# power_board.net
KiCad netlist of a schematic drawn in Altium Designer
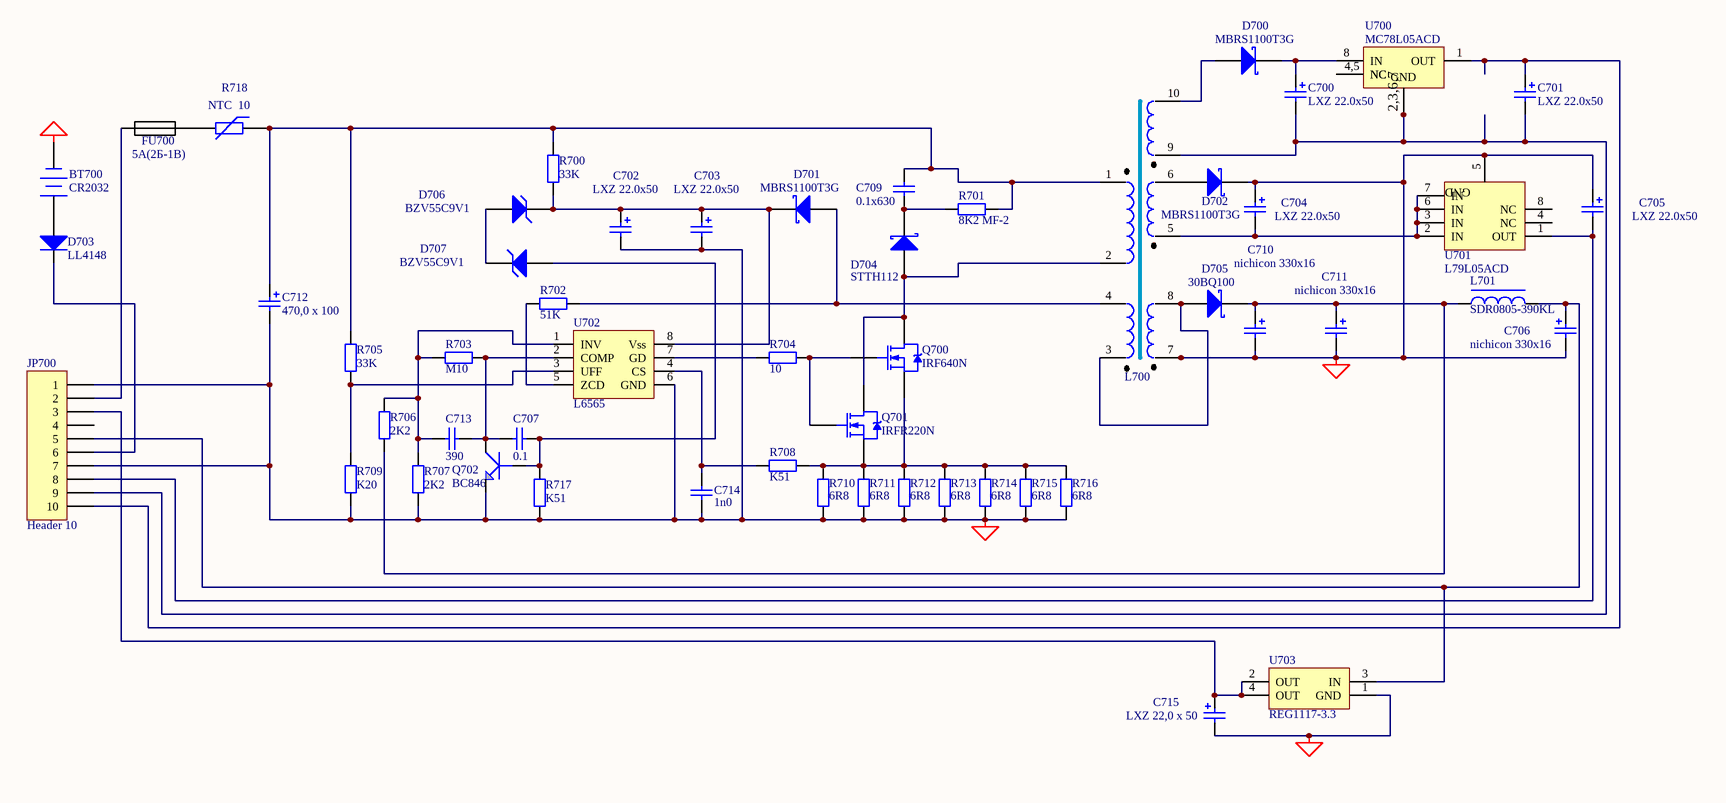
[diagram p0: power_board.SchDoc]

(export (version "E")
  (design (tool "Eeschema 10.0.6"))
  (components
    (comp (ref "BT700")
      (value "CR2032")
      (footprint "BAT_SUPP")
      (description "Multicell Battery")
      (fields (field (name "MANUFACTURER") "Generic Components") (field (name "PUBLISHER") "Altium Limited"))
      (libsource (lib "Miscellaneous Devices") (part "Battery"))
    )
    (comp (ref "C700")
      (value "LXZ 22.0x50")
      (footprint "el3")
      (description "Polarized Capacitor (Radial)")
      (fields (field (name "MANUFACTURER") "Generic Components") (field (name "PUBLISHER") "Altium Limited"))
      (libsource (lib "PAL") (part "Cap Pol1"))
    )
    (comp (ref "C701")
      (value "LXZ 22.0x50")
      (footprint "el3")
      (description "Polarized Capacitor (Radial)")
      (fields (field (name "MANUFACTURER") "Generic Components") (field (name "PUBLISHER") "Altium Limited"))
      (libsource (lib "PAL") (part "Cap Pol1"))
    )
    (comp (ref "C702")
      (value "LXZ 22.0x50")
      (footprint "el3")
      (description "Polarized Capacitor (Radial)")
      (fields (field (name "MANUFACTURER") "Generic Components") (field (name "PUBLISHER") "Altium Limited"))
      (libsource (lib "PAL") (part "Cap Pol1"))
    )
    (comp (ref "C703")
      (value "LXZ 22.0x50")
      (footprint "el3")
      (description "Polarized Capacitor (Radial)")
      (fields (field (name "MANUFACTURER") "Generic Components") (field (name "PUBLISHER") "Altium Limited"))
      (libsource (lib "PAL") (part "Cap Pol1"))
    )
    (comp (ref "C704")
      (value "LXZ 22.0x50")
      (footprint "el3")
      (description "Polarized Capacitor (Radial)")
      (fields (field (name "MANUFACTURER") "Generic Components") (field (name "PUBLISHER") "Altium Limited"))
      (libsource (lib "PAL") (part "Cap Pol1"))
    )
    (comp (ref "C705")
      (value "LXZ 22.0x50")
      (footprint "el3")
      (description "Polarized Capacitor (Radial)")
      (fields (field (name "MANUFACTURER") "Generic Components") (field (name "PUBLISHER") "Altium Limited"))
      (libsource (lib "PAL") (part "Cap Pol1"))
    )
    (comp (ref "C706")
      (value "nichicon 330x16")
      (footprint "el5")
      (description "Polarized Capacitor (Radial)")
      (fields (field (name "MANUFACTURER") "Generic Components") (field (name "PUBLISHER") "Altium Limited"))
      (libsource (lib "PAL") (part "Cap Pol1"))
    )
    (comp (ref "C707")
      (value "0.1")
      (footprint "_1206")
      (description "Capacitor (Semiconductor SIM Model)")
      (fields (field (name "MANUFACTURER") "Generic Components") (field (name "PUBLISHER") "Altium Limited"))
      (libsource (lib "Miscellaneous Devices") (part "Cap Semi"))
    )
    (comp (ref "C709")
      (value "0.1x630")
      (footprint "c15")
      (description "Capacitor (Semiconductor SIM Model)")
      (fields (field (name "MANUFACTURER") "Generic Components") (field (name "PUBLISHER") "Altium Limited"))
      (libsource (lib "Miscellaneous Devices") (part "Cap Semi"))
    )
    (comp (ref "C710")
      (value "nichicon 330x16")
      (footprint "el5")
      (description "Polarized Capacitor (Radial)")
      (fields (field (name "MANUFACTURER") "Generic Components") (field (name "PUBLISHER") "Altium Limited"))
      (libsource (lib "PAL") (part "Cap Pol1"))
    )
    (comp (ref "C711")
      (value "nichicon 330x16")
      (footprint "el5")
      (description "Polarized Capacitor (Radial)")
      (fields (field (name "MANUFACTURER") "Generic Components") (field (name "PUBLISHER") "Altium Limited"))
      (libsource (lib "PAL") (part "Cap Pol1"))
    )
    (comp (ref "C712")
      (value "470,0 x 100")
      (footprint "el_15_25_h")
      (description "Polarized Capacitor (Radial)")
      (fields (field (name "MANUFACTURER") "Generic Components") (field (name "PUBLISHER") "Altium Limited"))
      (libsource (lib "PAL") (part "Cap Pol1"))
    )
    (comp (ref "C713")
      (value "390")
      (footprint "_1206")
      (description "Capacitor (Semiconductor SIM Model)")
      (fields (field (name "MANUFACTURER") "Generic Components") (field (name "PUBLISHER") "Altium Limited"))
      (libsource (lib "Miscellaneous Devices") (part "Cap Semi"))
    )
    (comp (ref "C714")
      (value "1n0")
      (footprint "_1206")
      (description "Capacitor (Semiconductor SIM Model)")
      (fields (field (name "MANUFACTURER") "Generic Components") (field (name "PUBLISHER") "Altium Limited"))
      (libsource (lib "Miscellaneous Devices") (part "Cap Semi"))
    )
    (comp (ref "C715")
      (value "LXZ 22,0 x 50")
      (footprint "el3")
      (description "Polarized Capacitor (Radial)")
      (fields (field (name "MANUFACTURER") "Generic Components") (field (name "PUBLISHER") "Altium Limited"))
      (libsource (lib "PAL") (part "Cap Pol1"))
    )
    (comp (ref "D700")
      (value "MBRS1100T3G")
      (footprint "D_6_3")
      (description "Schottky Rectifier")
      (fields
        (field (name "MANUFACTURER") "International Rectifier")
        (field (name "PUBLISHER") "Altium Limited")
      )
      (libsource (lib "IR Discrete Diode") (part "10BQ015"))
    )
    (comp (ref "D701")
      (value "MBRS1100T3G")
      (footprint "D_6_3")
      (description "Schottky Rectifier")
      (fields
        (field (name "MANUFACTURER") "International Rectifier")
        (field (name "PUBLISHER") "Altium Limited")
      )
      (libsource (lib "IR Discrete Diode") (part "10BQ015"))
    )
    (comp (ref "D702")
      (value "MBRS1100T3G")
      (footprint "D_6_3")
      (description "Schottky Rectifier")
      (fields
        (field (name "MANUFACTURER") "International Rectifier")
        (field (name "PUBLISHER") "Altium Limited")
      )
      (libsource (lib "IR Discrete Diode") (part "10BQ015"))
    )
    (comp (ref "D703")
      (value "LL4148")
      (footprint "_1206d")
      (description "Default Diode")
      (fields (field (name "MANUFACTURER") "Generic Components") (field (name "PUBLISHER") "Altium Limited"))
      (libsource (lib "PAL") (part "Diode"))
    )
    (comp (ref "D704")
      (value "STTH112")
      (footprint "D_6_3")
      (description "Schottky Diode")
      (fields
        (field (name "MANUFACTURER") "International Rectifier")
        (field (name "PUBLISHER") "Altium Limited")
      )
      (libsource (lib "IR Discrete Diode") (part "10BQ015"))
    )
    (comp (ref "D705")
      (value "30BQ100")
      (footprint "30BQ100")
      (description "Schottky Rectifier")
      (fields
        (field (name "MANUFACTURER") "International Rectifier")
        (field (name "PUBLISHER") "Altium Limited")
      )
      (libsource (lib "IR Discrete Diode") (part "10BQ015"))
    )
    (comp (ref "D706")
      (value "BZV55C9V1")
      (footprint "_1206d")
      (description "Zener Diode")
      (fields (field (name "MANUFACTURER") "Generic Components") (field (name "PUBLISHER") "Altium Limited"))
      (libsource (lib "Miscellaneous Devices") (part "D Zener"))
    )
    (comp (ref "D707")
      (value "BZV55C9V1")
      (footprint "_1206d")
      (description "Zener Diode")
      (fields (field (name "MANUFACTURER") "Generic Components") (field (name "PUBLISHER") "Altium Limited"))
      (libsource (lib "Miscellaneous Devices") (part "D Zener"))
    )
    (comp (ref "FU700") (value "5A(2Б-1В)") (footprint "FUSE2") (libsource (lib "PAL") (part "FUSE")))
    (comp (ref "JP700")
      (value "Header 10")
      (footprint "HDR2X5")
      (description "Header, 10-Pin")
      (fields (field (name "MANUFACTURER") "Generic Components") (field (name "PUBLISHER") "Altium Limited"))
      (libsource (lib "Miscellaneous Connectors") (part "Header 10"))
    )
    (comp (ref "L700")
      (value "L220-K10")
      (footprint "trans_ring1")
      (description "Дроссель")
      (libsource (lib "PAL") (part "L1_dc_2"))
    )
    (comp (ref "L701")
      (value "SDR0805-390KL")
      (footprint "L10x10")
      (description "Magnetic-Core Inductor")
      (fields (field (name "MANUFACTURER") "Generic Components") (field (name "PUBLISHER") "Altium Limited"))
      (libsource (lib "PAL") (part "Inductor Konstr 2"))
    )
    (comp (ref "Q700")
      (value "IRF640N")
      (footprint "TO220_h")
      (description "N-Channel Power MOSFET")
      (fields (field (name "MANUFACTURER") "Generic Components") (field (name "PUBLISHER") "Altium Limited"))
      (libsource (lib "Miscellaneous Devices") (part "NMOS-2"))
    )
    (comp (ref "Q701")
      (value "IRFR220N")
      (footprint "SIP-G3/E13")
      (description "N-Channel Power MOSFET")
      (fields (field (name "MANUFACTURER") "Generic Components") (field (name "PUBLISHER") "Altium Limited"))
      (libsource (lib "Miscellaneous Devices") (part "NMOS-2"))
    )
    (comp (ref "Q702")
      (value "BC846")
      (footprint "SO-G3")
      (description "Bipolar transistor")
      (libsource (lib "MAIN") (part "GT122"))
    )
    (comp (ref "R700")
      (value "33K")
      (footprint "_1206")
      (description "Resistor")
      (fields (field (name "MANUFACTURER") "Generic Components") (field (name "PUBLISHER") "Altium Limited"))
      (libsource (lib "Miscellaneous Devices") (part "Res2"))
    )
    (comp (ref "R701")
      (value "8K2 MF-2")
      (footprint "AXIAL-0.7")
      (description "Resistor")
      (fields (field (name "MANUFACTURER") "Generic Components") (field (name "PUBLISHER") "Altium Limited"))
      (libsource (lib "") (part "Res2_2"))
    )
    (comp (ref "R702")
      (value "51K")
      (footprint "_1206")
      (description "Resistor")
      (fields (field (name "MANUFACTURER") "Generic Components") (field (name "PUBLISHER") "Altium Limited"))
      (libsource (lib "") (part "Res2_2"))
    )
    (comp (ref "R703")
      (value "M10")
      (footprint "_1206")
      (description "Resistor")
      (fields (field (name "MANUFACTURER") "Generic Components") (field (name "PUBLISHER") "Altium Limited"))
      (libsource (lib "") (part "Res2_2"))
    )
    (comp (ref "R704")
      (value "10")
      (footprint "_1206")
      (description "Resistor")
      (fields (field (name "MANUFACTURER") "Generic Components") (field (name "PUBLISHER") "Altium Limited"))
      (libsource (lib "") (part "Res2_2"))
    )
    (comp (ref "R705")
      (value "33K")
      (footprint "_1206")
      (description "Resistor")
      (fields (field (name "MANUFACTURER") "Generic Components") (field (name "PUBLISHER") "Altium Limited"))
      (libsource (lib "") (part "Res2_1"))
    )
    (comp (ref "R706")
      (value "2K2")
      (footprint "_1206")
      (description "Resistor")
      (fields (field (name "MANUFACTURER") "Generic Components") (field (name "PUBLISHER") "Altium Limited"))
      (libsource (lib "") (part "Res2_1"))
    )
    (comp (ref "R707")
      (value "2K2")
      (footprint "_1206")
      (description "Resistor")
      (fields (field (name "MANUFACTURER") "Generic Components") (field (name "PUBLISHER") "Altium Limited"))
      (libsource (lib "") (part "Res2_1"))
    )
    (comp (ref "R708")
      (value "K51")
      (footprint "_1206")
      (description "Resistor")
      (fields (field (name "MANUFACTURER") "Generic Components") (field (name "PUBLISHER") "Altium Limited"))
      (libsource (lib "") (part "Res2_2"))
    )
    (comp (ref "R709")
      (value "K20")
      (footprint "_1206")
      (description "Resistor")
      (fields (field (name "MANUFACTURER") "Generic Components") (field (name "PUBLISHER") "Altium Limited"))
      (libsource (lib "") (part "Res2_1"))
    )
    (comp (ref "R710")
      (value "6R8")
      (footprint "_1206")
      (description "Resistor")
      (fields (field (name "MANUFACTURER") "Generic Components") (field (name "PUBLISHER") "Altium Limited"))
      (libsource (lib "Miscellaneous Devices") (part "Res2"))
    )
    (comp (ref "R711")
      (value "6R8")
      (footprint "_1206")
      (description "Resistor")
      (fields (field (name "MANUFACTURER") "Generic Components") (field (name "PUBLISHER") "Altium Limited"))
      (libsource (lib "Miscellaneous Devices") (part "Res2"))
    )
    (comp (ref "R712")
      (value "6R8")
      (footprint "_1206")
      (description "Resistor")
      (fields (field (name "MANUFACTURER") "Generic Components") (field (name "PUBLISHER") "Altium Limited"))
      (libsource (lib "Miscellaneous Devices") (part "Res2"))
    )
    (comp (ref "R713")
      (value "6R8")
      (footprint "_1206")
      (description "Resistor")
      (fields (field (name "MANUFACTURER") "Generic Components") (field (name "PUBLISHER") "Altium Limited"))
      (libsource (lib "Miscellaneous Devices") (part "Res2"))
    )
    (comp (ref "R714")
      (value "6R8")
      (footprint "_1206")
      (description "Resistor")
      (fields (field (name "MANUFACTURER") "Generic Components") (field (name "PUBLISHER") "Altium Limited"))
      (libsource (lib "Miscellaneous Devices") (part "Res2"))
    )
    (comp (ref "R715")
      (value "6R8")
      (footprint "_1206")
      (description "Resistor")
      (fields (field (name "MANUFACTURER") "Generic Components") (field (name "PUBLISHER") "Altium Limited"))
      (libsource (lib "Miscellaneous Devices") (part "Res2"))
    )
    (comp (ref "R716")
      (value "6R8")
      (footprint "_1206")
      (description "Resistor")
      (fields (field (name "MANUFACTURER") "Generic Components") (field (name "PUBLISHER") "Altium Limited"))
      (libsource (lib "Miscellaneous Devices") (part "Res2"))
    )
    (comp (ref "R717")
      (value "K51")
      (footprint "_1206")
      (description "Resistor")
      (fields (field (name "MANUFACTURER") "Generic Components") (field (name "PUBLISHER") "Altium Limited"))
      (libsource (lib "") (part "Res2_1"))
    )
    (comp (ref "R718")
      (value "NTC  10")
      (footprint "JVR07N")
      (description "Varistor (Voltage-Sensitive Resistor)")
      (fields (field (name "MANUFACTURER") "Generic Components") (field (name "PUBLISHER") "Altium Limited"))
      (libsource (lib "Miscellaneous Devices") (part "Res Varistor"))
    )
    (comp (ref "U700")
      (value "MC78L05ACD")
      (footprint "SO-G8")
      (description "3-Terminal Low-Current Positive Fixed Voltage Regulator")
      (fields (field (name "MANUFACTURER") "Motorola") (field (name "PUBLISHER") "Altium Limited"))
      (libsource (lib "Motorola Power Management Voltage Regulator") (part "MC78L05ACD"))
    )
    (comp (ref "U701")
      (value "L79L05ACD")
      (footprint "SO-G8")
      (description "Negative Voltage Regulator")
      (fields (field (name "MANUFACTURER") "ST-Microelectronics") (field (name "PUBLISHER") "Altium Limited"))
      (libsource (lib "ST Power Mgt Voltage Regulator") (part "L79L05ACD"))
    )
    (comp (ref "U702") (value "L6565") (footprint "so-g8") (libsource (lib "PAL") (part "L6565")))
    (comp (ref "U703")
      (value "REG1117-3.3")
      (footprint "DSO-G3")
      (description "800mA and 1A Low Dropout Positive Regulator 2.85V, 3.3V, 5V, and Adjustable")
      (fields (field (name "MANUFACTURER") "Burr-Brown") (field (name "PUBLISHER") "Altium Limited"))
      (libsource (lib "BB Power Mgt Voltage Regulator") (part "REG1117-3.3"))
    )
  )
  (nets
    (net (code "1") (name "GND_p") (class "Default")
      (node (ref "BT700") (pin "2") (pinfunction "-_2") (pintype "passive"))
      (node (ref "C702") (pin "2") (pinfunction "2_2") (pintype "passive"))
      (node (ref "C703") (pin "2") (pinfunction "2_2") (pintype "passive"))
      (node (ref "C704") (pin "1") (pinfunction "1_1") (pintype "passive"))
      (node (ref "C705") (pin "1") (pinfunction "1_1") (pintype "passive"))
      (node (ref "C706") (pin "2") (pinfunction "2_2") (pintype "passive"))
      (node (ref "C710") (pin "2") (pinfunction "2_2") (pintype "passive"))
      (node (ref "C711") (pin "2") (pinfunction "2_2") (pintype "passive"))
      (node (ref "C712") (pin "2") (pinfunction "2_2") (pintype "passive"))
      (node (ref "C714") (pin "2") (pinfunction "2_2") (pintype "passive"))
      (node (ref "C715") (pin "2") (pinfunction "2_2") (pintype "passive"))
      (node (ref "D702") (pin "2") (pinfunction "K_2") (pintype "passive"))
      (node (ref "JP700") (pin "1") (pinfunction "1_1") (pintype "passive"))
      (node (ref "JP700") (pin "7") (pinfunction "7_7") (pintype "passive"))
      (node (ref "L700") (pin "7") (pintype "passive"))
      (node (ref "Q702") (pin "2") (pinfunction "E_2") (pintype "passive"))
      (node (ref "R707") (pin "1") (pinfunction "1_1") (pintype "passive"))
      (node (ref "R709") (pin "1") (pinfunction "1_1") (pintype "passive"))
      (node (ref "R710") (pin "2") (pinfunction "2_2") (pintype "passive"))
      (node (ref "R711") (pin "2") (pinfunction "2_2") (pintype "passive"))
      (node (ref "R712") (pin "2") (pinfunction "2_2") (pintype "passive"))
      (node (ref "R713") (pin "2") (pinfunction "2_2") (pintype "passive"))
      (node (ref "R714") (pin "2") (pinfunction "2_2") (pintype "passive"))
      (node (ref "R715") (pin "2") (pinfunction "2_2") (pintype "passive"))
      (node (ref "R716") (pin "2") (pinfunction "2_2") (pintype "passive"))
      (node (ref "R717") (pin "1") (pinfunction "1_1") (pintype "passive"))
      (node (ref "U701") (pin "5") (pinfunction "GND_5") (pintype "power_in"))
      (node (ref "U702") (pin "6") (pinfunction "GND_6") (pintype "passive"))
      (node (ref "U703") (pin "1") (pinfunction "GND_1") (pintype "power_in"))
    )
    (net (code "2") (name "Net-(BT700-+)") (class "Default")
      (node (ref "BT700") (pin "1") (pinfunction "+_1") (pintype "passive"))
      (node (ref "D703") (pin "1") (pinfunction "A_1") (pintype "passive"))
    )
    (net (code "3") (name "Net-(C700-Pad2)") (class "Default")
      (node (ref "C700") (pin "2") (pinfunction "2_2") (pintype "passive"))
      (node (ref "C701") (pin "2") (pinfunction "2_2") (pintype "passive"))
      (node (ref "JP700") (pin "9") (pinfunction "9_9") (pintype "passive"))
      (node (ref "L700") (pin "9") (pintype "passive"))
      (node (ref "U700") (pin "2") (pinfunction "GND_2") (pintype "power_in"))
      (node (ref "U700") (pin "3") (pinfunction "GND_3") (pintype "power_in"))
      (node (ref "U700") (pin "6") (pinfunction "GND_6") (pintype "power_in"))
      (node (ref "U700") (pin "7") (pinfunction "GND_7") (pintype "power_in"))
    )
    (net (code "4") (name "Net-(C704-Pad2)") (class "Default")
      (node (ref "C704") (pin "2") (pinfunction "2_2") (pintype "passive"))
      (node (ref "L700") (pin "5") (pintype "passive"))
      (node (ref "U701") (pin "2") (pinfunction "IN_2") (pintype "power_in"))
      (node (ref "U701") (pin "3") (pinfunction "IN_3") (pintype "power_in"))
      (node (ref "U701") (pin "6") (pinfunction "IN_6") (pintype "power_in"))
      (node (ref "U701") (pin "7") (pinfunction "IN_7") (pintype "power_in"))
    )
    (net (code "5") (name "Net-(C709-Pad2)") (class "Default")
      (node (ref "C709") (pin "2") (pinfunction "2_2") (pintype "passive"))
      (node (ref "C712") (pin "1") (pinfunction "1_1") (pintype "passive"))
      (node (ref "L700") (pin "1") (pintype "passive"))
      (node (ref "R700") (pin "1") (pinfunction "1_1") (pintype "passive"))
      (node (ref "R701") (pin "1") (pinfunction "1_1") (pintype "passive"))
      (node (ref "R705") (pin "2") (pinfunction "2_2") (pintype "passive"))
      (node (ref "R718") (pin "1") (pinfunction "1_1") (pintype "passive"))
    )
    (net (code "6") (name "Net-(C715-Pad1)") (class "Default")
      (node (ref "C715") (pin "1") (pinfunction "1_1") (pintype "passive"))
      (node (ref "JP700") (pin "3") (pinfunction "3_3") (pintype "passive"))
      (node (ref "U703") (pin "2") (pinfunction "OUT_2") (pintype "power_in"))
      (node (ref "U703") (pin "4") (pinfunction "OUT_4") (pintype "power_in"))
    )
    (net (code "7") (name "Net-(D700-A)") (class "Default")
      (node (ref "D700") (pin "1") (pinfunction "A_1") (pintype "passive"))
      (node (ref "L700") (pin "10") (pinfunction "10_10") (pintype "passive"))
    )
    (net (code "8") (name "Net-(D700-K)") (class "Default")
      (node (ref "C700") (pin "1") (pinfunction "1_1") (pintype "passive"))
      (node (ref "D700") (pin "2") (pinfunction "K_2") (pintype "passive"))
      (node (ref "U700") (pin "8") (pinfunction "IN_8") (pintype "power_in"))
    )
    (net (code "9") (name "Net-(D701-A)") (class "Default")
      (node (ref "D701") (pin "1") (pinfunction "A_1") (pintype "passive"))
      (node (ref "L700") (pin "4") (pintype "passive"))
      (node (ref "R702") (pin "1") (pinfunction "1_1") (pintype "passive"))
    )
    (net (code "10") (name "Net-(D701-K)") (class "Default")
      (node (ref "C702") (pin "1") (pinfunction "1_1") (pintype "passive"))
      (node (ref "C703") (pin "1") (pinfunction "1_1") (pintype "passive"))
      (node (ref "D701") (pin "2") (pinfunction "K_2") (pintype "passive"))
      (node (ref "D706") (pin "2") (pinfunction "K_2") (pintype "passive"))
      (node (ref "R700") (pin "2") (pinfunction "2_2") (pintype "passive"))
      (node (ref "U702") (pin "8") (pinfunction "Vss_8") (pintype "passive"))
    )
    (net (code "11") (name "Net-(D702-A)") (class "Default")
      (node (ref "D702") (pin "1") (pinfunction "A_1") (pintype "passive"))
      (node (ref "L700") (pin "6") (pintype "passive"))
    )
    (net (code "12") (name "Net-(D703-K)") (class "Default")
      (node (ref "D703") (pin "2") (pinfunction "K_2") (pintype "passive"))
      (node (ref "JP700") (pin "6") (pinfunction "6_6") (pintype "passive"))
    )
    (net (code "13") (name "Net-(D704-A)") (class "Default")
      (node (ref "D704") (pin "1") (pinfunction "A_1") (pintype "passive"))
      (node (ref "L700") (pin "2") (pintype "passive"))
      (node (ref "Q700") (pin "2") (pinfunction "D_2") (pintype "passive"))
      (node (ref "Q701") (pin "2") (pinfunction "D_2") (pintype "passive"))
    )
    (net (code "14") (name "Net-(D704-K)") (class "Default")
      (node (ref "C709") (pin "1") (pinfunction "1_1") (pintype "passive"))
      (node (ref "D704") (pin "2") (pinfunction "K_2") (pintype "passive"))
      (node (ref "R701") (pin "2") (pinfunction "2_2") (pintype "passive"))
    )
    (net (code "15") (name "Net-(D705-A)") (class "Default")
      (node (ref "D705") (pin "1") (pinfunction "A_1") (pintype "passive"))
      (node (ref "L700") (pin "3") (pintype "passive"))
      (node (ref "L700") (pin "8") (pintype "passive"))
    )
    (net (code "16") (name "Net-(D705-K)") (class "Default")
      (node (ref "C710") (pin "1") (pinfunction "1_1") (pintype "passive"))
      (node (ref "C711") (pin "1") (pinfunction "1_1") (pintype "passive"))
      (node (ref "D705") (pin "2") (pinfunction "K_2") (pintype "passive"))
      (node (ref "L701") (pin "2") (pinfunction "2_2") (pintype "passive"))
      (node (ref "R706") (pin "1") (pinfunction "1_1") (pintype "passive"))
    )
    (net (code "17") (name "Net-(D706-A)") (class "Default")
      (node (ref "D706") (pin "1") (pinfunction "A_1") (pintype "passive"))
      (node (ref "D707") (pin "2") (pinfunction "K_2") (pintype "passive"))
    )
    (net (code "18") (name "Net-(D707-A)") (class "Default")
      (node (ref "C707") (pin "2") (pinfunction "2_2") (pintype "passive"))
      (node (ref "D707") (pin "1") (pinfunction "A_1") (pintype "passive"))
      (node (ref "Q702") (pin "1") (pinfunction "B_1") (pintype "passive"))
      (node (ref "R717") (pin "2") (pinfunction "2_2") (pintype "passive"))
    )
    (net (code "19") (name "Net-(FU700-Pad1)") (class "Default")
      (node (ref "FU700") (pin "1") (pinfunction "1_1") (pintype "passive"))
      (node (ref "JP700") (pin "2") (pinfunction "2_2") (pintype "passive"))
    )
    (net (code "20") (name "Net-(FU700-Pad2)") (class "Default")
      (node (ref "FU700") (pin "2") (pinfunction "2_2") (pintype "passive"))
      (node (ref "R718") (pin "2") (pinfunction "2_2") (pintype "passive"))
    )
    (net (code "21") (name "Net-(Q700-G)") (class "Default")
      (node (ref "Q700") (pin "1") (pinfunction "G_1") (pintype "passive"))
      (node (ref "Q701") (pin "1") (pinfunction "G_1") (pintype "passive"))
      (node (ref "R704") (pin "1") (pinfunction "1_1") (pintype "passive"))
    )
    (net (code "22") (name "Net-(Q700-S)") (class "Default")
      (node (ref "Q700") (pin "3") (pinfunction "S_3") (pintype "passive"))
      (node (ref "Q701") (pin "3") (pinfunction "S_3") (pintype "passive"))
      (node (ref "R708") (pin "1") (pinfunction "1_1") (pintype "passive"))
      (node (ref "R710") (pin "1") (pinfunction "1_1") (pintype "passive"))
      (node (ref "R711") (pin "1") (pinfunction "1_1") (pintype "passive"))
      (node (ref "R712") (pin "1") (pinfunction "1_1") (pintype "passive"))
      (node (ref "R713") (pin "1") (pinfunction "1_1") (pintype "passive"))
      (node (ref "R714") (pin "1") (pinfunction "1_1") (pintype "passive"))
      (node (ref "R715") (pin "1") (pinfunction "1_1") (pintype "passive"))
      (node (ref "R716") (pin "1") (pinfunction "1_1") (pintype "passive"))
    )
    (net (code "23") (name "Net-(Q702-C)") (class "Default")
      (node (ref "C707") (pin "1") (pinfunction "1_1") (pintype "passive"))
      (node (ref "C713") (pin "2") (pinfunction "2_2") (pintype "passive"))
      (node (ref "Q702") (pin "3") (pinfunction "C_3") (pintype "passive"))
      (node (ref "R703") (pin "1") (pinfunction "1_1") (pintype "passive"))
      (node (ref "U702") (pin "2") (pinfunction "COMP_2") (pintype "passive"))
    )
    (net (code "24") (name "Net-(U700-NC-Pad4)") (class "Default")
      (node (ref "U700") (pin "4") (pinfunction "NC_4") (pintype "passive"))
      (node (ref "U700") (pin "5") (pinfunction "NC_5") (pintype "passive"))
    )
    (net (code "25") (name "Net-(U700-OUT)") (class "Default")
      (node (ref "C701") (pin "1") (pinfunction "1_1") (pintype "passive"))
      (node (ref "JP700") (pin "10") (pinfunction "10_10") (pintype "passive"))
      (node (ref "U700") (pin "1") (pinfunction "OUT_1") (pintype "power_in"))
    )
    (net (code "26") (name "Net-(U701-OUT)") (class "Default")
      (node (ref "C705") (pin "2") (pinfunction "2_2") (pintype "passive"))
      (node (ref "JP700") (pin "8") (pinfunction "8_8") (pintype "passive"))
      (node (ref "U701") (pin "1") (pinfunction "OUT_1") (pintype "power_in"))
    )
    (net (code "27") (name "Net-(U702-CS)") (class "Default")
      (node (ref "C714") (pin "1") (pinfunction "1_1") (pintype "passive"))
      (node (ref "R708") (pin "2") (pinfunction "2_2") (pintype "passive"))
      (node (ref "U702") (pin "4") (pinfunction "CS_4") (pintype "passive"))
    )
    (net (code "28") (name "Net-(U702-GD)") (class "Default")
      (node (ref "R704") (pin "2") (pinfunction "2_2") (pintype "passive"))
      (node (ref "U702") (pin "7") (pinfunction "GD_7") (pintype "passive"))
    )
    (net (code "29") (name "Net-(U702-INV)") (class "Default")
      (node (ref "C713") (pin "1") (pinfunction "1_1") (pintype "passive"))
      (node (ref "R703") (pin "2") (pinfunction "2_2") (pintype "passive"))
      (node (ref "R706") (pin "2") (pinfunction "2_2") (pintype "passive"))
      (node (ref "R707") (pin "2") (pinfunction "2_2") (pintype "passive"))
      (node (ref "U702") (pin "1") (pinfunction "INV_1") (pintype "passive"))
    )
    (net (code "30") (name "Net-(U702-UFF)") (class "Default")
      (node (ref "R705") (pin "1") (pinfunction "1_1") (pintype "passive"))
      (node (ref "R709") (pin "2") (pinfunction "2_2") (pintype "passive"))
      (node (ref "U702") (pin "3") (pinfunction "UFF_3") (pintype "passive"))
    )
    (net (code "31") (name "Net-(U702-ZCD)") (class "Default")
      (node (ref "R702") (pin "2") (pinfunction "2_2") (pintype "passive"))
      (node (ref "U702") (pin "5") (pinfunction "ZCD_5") (pintype "passive"))
    )
    (net (code "32") (name "Net-(U703-IN)") (class "Default")
      (node (ref "C706") (pin "1") (pinfunction "1_1") (pintype "passive"))
      (node (ref "JP700") (pin "5") (pinfunction "5_5") (pintype "passive"))
      (node (ref "L701") (pin "1") (pinfunction "1_1") (pintype "passive"))
      (node (ref "U703") (pin "3") (pinfunction "IN_3") (pintype "power_in"))
    )
    (net (code "33") (name "unconnected-(JP700-Pad4)") (class "Default")
      (node (ref "JP700") (pin "4") (pinfunction "4_4") (pintype "passive"))
    )
    (net (code "34") (name "unconnected-(U701-NC-Pad4)") (class "Default")
      (node (ref "U701") (pin "4") (pinfunction "NC_4") (pintype "passive"))
    )
    (net (code "35") (name "unconnected-(U701-NC-Pad8)") (class "Default")
      (node (ref "U701") (pin "8") (pinfunction "NC_8") (pintype "passive"))
    )
  )
)
